# USB-RS485_ConversionAdapter.net
KiCad netlist of a schematic drawn in EAGLE
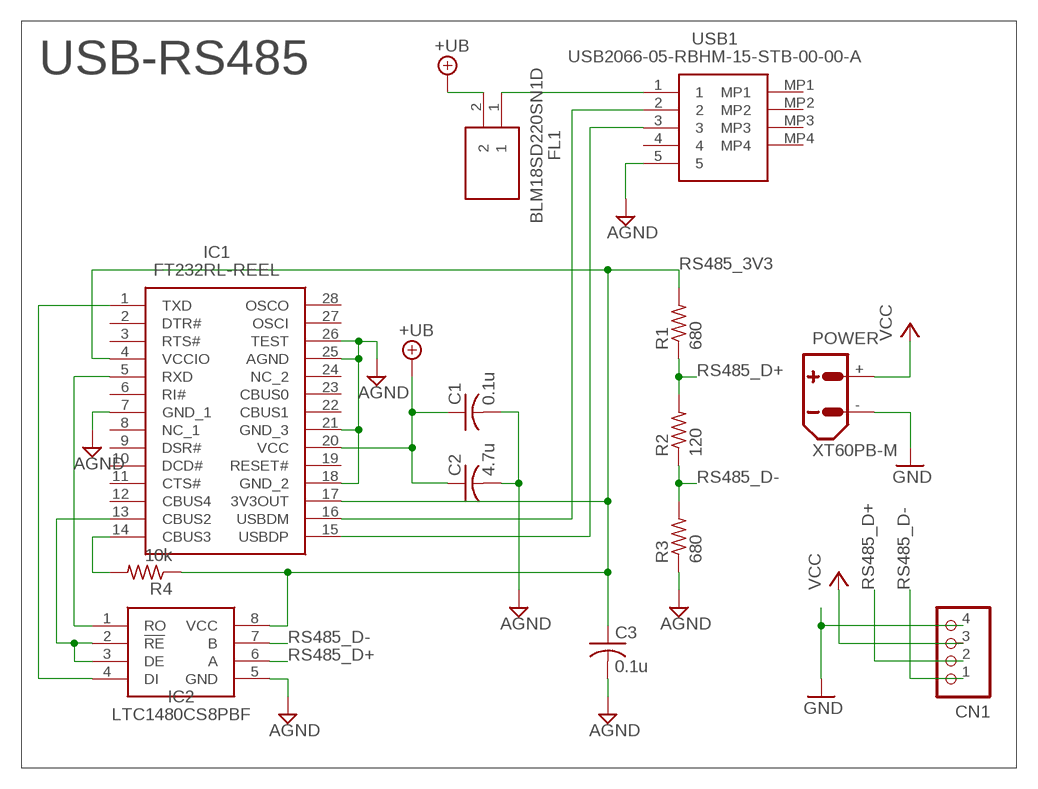
[diagram p0: schematic, sheet 1]

(export (version "E")
  (design (tool "Eeschema 10.0.6"))
  (components
    (comp (ref "C1")
      (value "0.1u")
      (footprint "eagle-import:C1608")
      (libsource (lib "eagle-import") (part "C-USC1608"))
    )
    (comp (ref "C2")
      (value "4.7u")
      (footprint "eagle-import:C1608")
      (libsource (lib "eagle-import") (part "C-USC1608"))
    )
    (comp (ref "C3")
      (value "0.1u")
      (footprint "eagle-import:C1608")
      (libsource (lib "eagle-import") (part "C-USC1608"))
    )
    (comp (ref "CN1")
      (value "B4B-XH-A")
      (footprint "eagle-import:B4B-XH-A")
      (libsource (lib "eagle-import") (part "B4B-XH-A"))
    )
    (comp (ref "FL1")
      (value "BLM18SD220SN1D")
      (footprint "eagle-import:BLM18AG102BH1D")
      (fields (field (name "MOUSER_PART_NUMBER") "81-BLM18SD220SN1D"))
      (libsource (lib "eagle-import") (part "BLM18SD220SN1D"))
    )
    (comp (ref "IC1")
      (value "FT232RL-REEL")
      (footprint "eagle-import:SOP65P778X200-28N")
      (fields (field (name "MOUSER_PART_NUMBER") "895-FT232RL"))
      (libsource (lib "eagle-import") (part "FT232RL-REEL"))
    )
    (comp (ref "IC2")
      (value "LTC1480CS8PBF")
      (footprint "eagle-import:SOIC127P599X175-8N")
      (libsource (lib "eagle-import") (part "LTC1480CS8PBF"))
    )
    (comp (ref "POWER")
      (value "XT60PB-M")
      (footprint "eagle-import:XT60PB-M")
      (libsource (lib "eagle-import") (part "XT60PB-M"))
    )
    (comp (ref "R1")
      (value "680")
      (footprint "eagle-import:R0603")
      (libsource (lib "eagle-import") (part "R-US_R0603"))
    )
    (comp (ref "R2")
      (value "120")
      (footprint "eagle-import:R0603")
      (libsource (lib "eagle-import") (part "R-US_R0603"))
    )
    (comp (ref "R3")
      (value "680")
      (footprint "eagle-import:R0603")
      (libsource (lib "eagle-import") (part "R-US_R0603"))
    )
    (comp (ref "R4")
      (value "10k")
      (footprint "eagle-import:R0603")
      (libsource (lib "eagle-import") (part "R-US_R0603"))
    )
    (comp (ref "USB1")
      (value "USB2066-05-RBHM-15-STB-00-00-A")
      (footprint "eagle-import:USB206605RBHM15STB0000A")
      (fields (field (name "MOUSER_PART_NUMBER") "640-2665RBHM15STB00A"))
      (libsource (lib "eagle-import") (part "USB2066-05-RBHM-15-STB-00-00-A"))
    )
  )
  (nets
    (net (code "1") (name "+UB") (class "Default")
      (node (ref "C1") (pin "1") (pinfunction "1_1") (pintype "passive"))
      (node (ref "C2") (pin "1") (pinfunction "1_1") (pintype "passive"))
      (node (ref "FL1") (pin "2") (pinfunction "2_2") (pintype "bidirectional"))
      (node (ref "IC1") (pin "20") (pinfunction "VCC_20") (pintype "bidirectional"))
    )
    (net (code "2") (name "/RS485_3V3") (class "Default")
      (node (ref "C3") (pin "1") (pinfunction "1_1") (pintype "passive"))
      (node (ref "IC1") (pin "17") (pinfunction "3V3OUT_17") (pintype "bidirectional"))
      (node (ref "IC1") (pin "4") (pinfunction "VCCIO_4") (pintype "bidirectional"))
      (node (ref "IC2") (pin "8") (pinfunction "VCC_8") (pintype "bidirectional"))
      (node (ref "R1") (pin "2") (pinfunction "2_2") (pintype "passive"))
      (node (ref "R4") (pin "1") (pinfunction "1_1") (pintype "passive"))
    )
    (net (code "3") (name "/RS485_D+") (class "Default")
      (node (ref "CN1") (pin "2") (pinfunction "2_2") (pintype "passive"))
      (node (ref "IC2") (pin "6") (pinfunction "A_6") (pintype "bidirectional"))
      (node (ref "R1") (pin "1") (pinfunction "1_1") (pintype "passive"))
      (node (ref "R2") (pin "2") (pinfunction "2_2") (pintype "passive"))
    )
    (net (code "4") (name "/RS485_D-") (class "Default")
      (node (ref "CN1") (pin "1") (pinfunction "1_1") (pintype "passive"))
      (node (ref "IC2") (pin "7") (pinfunction "B_7") (pintype "bidirectional"))
      (node (ref "R2") (pin "1") (pinfunction "1_1") (pintype "passive"))
      (node (ref "R3") (pin "2") (pinfunction "2_2") (pintype "passive"))
    )
    (net (code "5") (name "AGND") (class "Default")
      (node (ref "C1") (pin "2") (pinfunction "2_2") (pintype "passive"))
      (node (ref "C2") (pin "2") (pinfunction "2_2") (pintype "passive"))
      (node (ref "C3") (pin "2") (pinfunction "2_2") (pintype "passive"))
      (node (ref "IC1") (pin "18") (pinfunction "GND_2_18") (pintype "bidirectional"))
      (node (ref "IC1") (pin "21") (pinfunction "GND_3_21") (pintype "bidirectional"))
      (node (ref "IC1") (pin "25") (pinfunction "AGND_25") (pintype "bidirectional"))
      (node (ref "IC1") (pin "26") (pinfunction "TEST_26") (pintype "bidirectional"))
      (node (ref "IC1") (pin "7") (pinfunction "GND_1_7") (pintype "bidirectional"))
      (node (ref "IC2") (pin "5") (pinfunction "GND_5") (pintype "bidirectional"))
      (node (ref "R3") (pin "1") (pinfunction "1_1") (pintype "passive"))
      (node (ref "USB1") (pin "5") (pinfunction "5_5") (pintype "bidirectional"))
    )
    (net (code "6") (name "GND") (class "Default")
      (node (ref "CN1") (pin "4") (pinfunction "4_4") (pintype "passive"))
      (node (ref "POWER") (pin "-") (pinfunction "-_-") (pintype "power_in"))
    )
    (net (code "7") (name "Net-(FL1-Pad1)") (class "Default")
      (node (ref "FL1") (pin "1") (pinfunction "1_1") (pintype "bidirectional"))
      (node (ref "USB1") (pin "1") (pinfunction "1_1") (pintype "bidirectional"))
    )
    (net (code "8") (name "Net-(IC1-CBUS2)") (class "Default")
      (node (ref "IC1") (pin "13") (pinfunction "CBUS2_13") (pintype "bidirectional"))
      (node (ref "IC2") (pin "2") (pinfunction "~{RE}_2") (pintype "bidirectional"))
      (node (ref "IC2") (pin "3") (pinfunction "DE_3") (pintype "bidirectional"))
    )
    (net (code "9") (name "Net-(IC1-CBUS3)") (class "Default")
      (node (ref "IC1") (pin "14") (pinfunction "CBUS3_14") (pintype "bidirectional"))
      (node (ref "R4") (pin "2") (pinfunction "2_2") (pintype "passive"))
    )
    (net (code "10") (name "Net-(IC1-RXD)") (class "Default")
      (node (ref "IC1") (pin "5") (pinfunction "RXD_5") (pintype "bidirectional"))
      (node (ref "IC2") (pin "1") (pinfunction "RO_1") (pintype "bidirectional"))
    )
    (net (code "11") (name "Net-(IC1-TXD)") (class "Default")
      (node (ref "IC1") (pin "1") (pinfunction "TXD_1") (pintype "bidirectional"))
      (node (ref "IC2") (pin "4") (pinfunction "DI_4") (pintype "bidirectional"))
    )
    (net (code "12") (name "Net-(IC1-USBDM)") (class "Default")
      (node (ref "IC1") (pin "16") (pinfunction "USBDM_16") (pintype "bidirectional"))
      (node (ref "USB1") (pin "2") (pinfunction "2_2") (pintype "bidirectional"))
    )
    (net (code "13") (name "Net-(IC1-USBDP)") (class "Default")
      (node (ref "IC1") (pin "15") (pinfunction "USBDP_15") (pintype "bidirectional"))
      (node (ref "USB1") (pin "3") (pinfunction "3_3") (pintype "bidirectional"))
    )
    (net (code "14") (name "VCC") (class "Default")
      (node (ref "CN1") (pin "3") (pinfunction "3_3") (pintype "passive"))
      (node (ref "POWER") (pin "+") (pinfunction "+_+") (pintype "power_in"))
    )
    (net (code "15") (name "unconnected-(IC1-CBUS0-Pad23)") (class "Default")
      (node (ref "IC1") (pin "23") (pinfunction "CBUS0_23") (pintype "bidirectional"))
    )
    (net (code "16") (name "unconnected-(IC1-CBUS1-Pad22)") (class "Default")
      (node (ref "IC1") (pin "22") (pinfunction "CBUS1_22") (pintype "bidirectional"))
    )
    (net (code "17") (name "unconnected-(IC1-CBUS4-Pad12)") (class "Default")
      (node (ref "IC1") (pin "12") (pinfunction "CBUS4_12") (pintype "bidirectional"))
    )
    (net (code "18") (name "unconnected-(IC1-CTS#-Pad11)") (class "Default")
      (node (ref "IC1") (pin "11") (pinfunction "CTS#_11") (pintype "bidirectional"))
    )
    (net (code "19") (name "unconnected-(IC1-DCD#-Pad10)") (class "Default")
      (node (ref "IC1") (pin "10") (pinfunction "DCD#_10") (pintype "bidirectional"))
    )
    (net (code "20") (name "unconnected-(IC1-DSR#-Pad9)") (class "Default")
      (node (ref "IC1") (pin "9") (pinfunction "DSR#_9") (pintype "bidirectional"))
    )
    (net (code "21") (name "unconnected-(IC1-DTR#-Pad2)") (class "Default")
      (node (ref "IC1") (pin "2") (pinfunction "DTR#_2") (pintype "bidirectional"))
    )
    (net (code "22") (name "unconnected-(IC1-NC_1-Pad8)") (class "Default")
      (node (ref "IC1") (pin "8") (pinfunction "NC_1_8") (pintype "bidirectional"))
    )
    (net (code "23") (name "unconnected-(IC1-NC_2-Pad24)") (class "Default")
      (node (ref "IC1") (pin "24") (pinfunction "NC_2_24") (pintype "bidirectional"))
    )
    (net (code "24") (name "unconnected-(IC1-OSCI-Pad27)") (class "Default")
      (node (ref "IC1") (pin "27") (pinfunction "OSCI_27") (pintype "bidirectional"))
    )
    (net (code "25") (name "unconnected-(IC1-OSCO-Pad28)") (class "Default")
      (node (ref "IC1") (pin "28") (pinfunction "OSCO_28") (pintype "bidirectional"))
    )
    (net (code "26") (name "unconnected-(IC1-RESET#-Pad19)") (class "Default")
      (node (ref "IC1") (pin "19") (pinfunction "RESET#_19") (pintype "bidirectional"))
    )
    (net (code "27") (name "unconnected-(IC1-RI#-Pad6)") (class "Default")
      (node (ref "IC1") (pin "6") (pinfunction "RI#_6") (pintype "bidirectional"))
    )
    (net (code "28") (name "unconnected-(IC1-RTS#-Pad3)") (class "Default")
      (node (ref "IC1") (pin "3") (pinfunction "RTS#_3") (pintype "bidirectional"))
    )
    (net (code "29") (name "unconnected-(USB1-Pad4)") (class "Default")
      (node (ref "USB1") (pin "4") (pinfunction "4_4") (pintype "bidirectional"))
    )
    (net (code "30") (name "unconnected-(USB1-PadMP1)") (class "Default")
      (node (ref "USB1") (pin "MP1") (pinfunction "MP1_MP1") (pintype "bidirectional"))
    )
    (net (code "31") (name "unconnected-(USB1-PadMP2)") (class "Default")
      (node (ref "USB1") (pin "MP2") (pinfunction "MP2_MP2") (pintype "bidirectional"))
    )
    (net (code "32") (name "unconnected-(USB1-PadMP3)") (class "Default")
      (node (ref "USB1") (pin "MP3") (pinfunction "MP3_MP3") (pintype "bidirectional"))
    )
    (net (code "33") (name "unconnected-(USB1-PadMP4)") (class "Default")
      (node (ref "USB1") (pin "MP4") (pinfunction "MP4_MP4") (pintype "bidirectional"))
    )
  )
)
